# 3_HV_Detection.net
KiCad netlist of a schematic drawn in Altium Designer
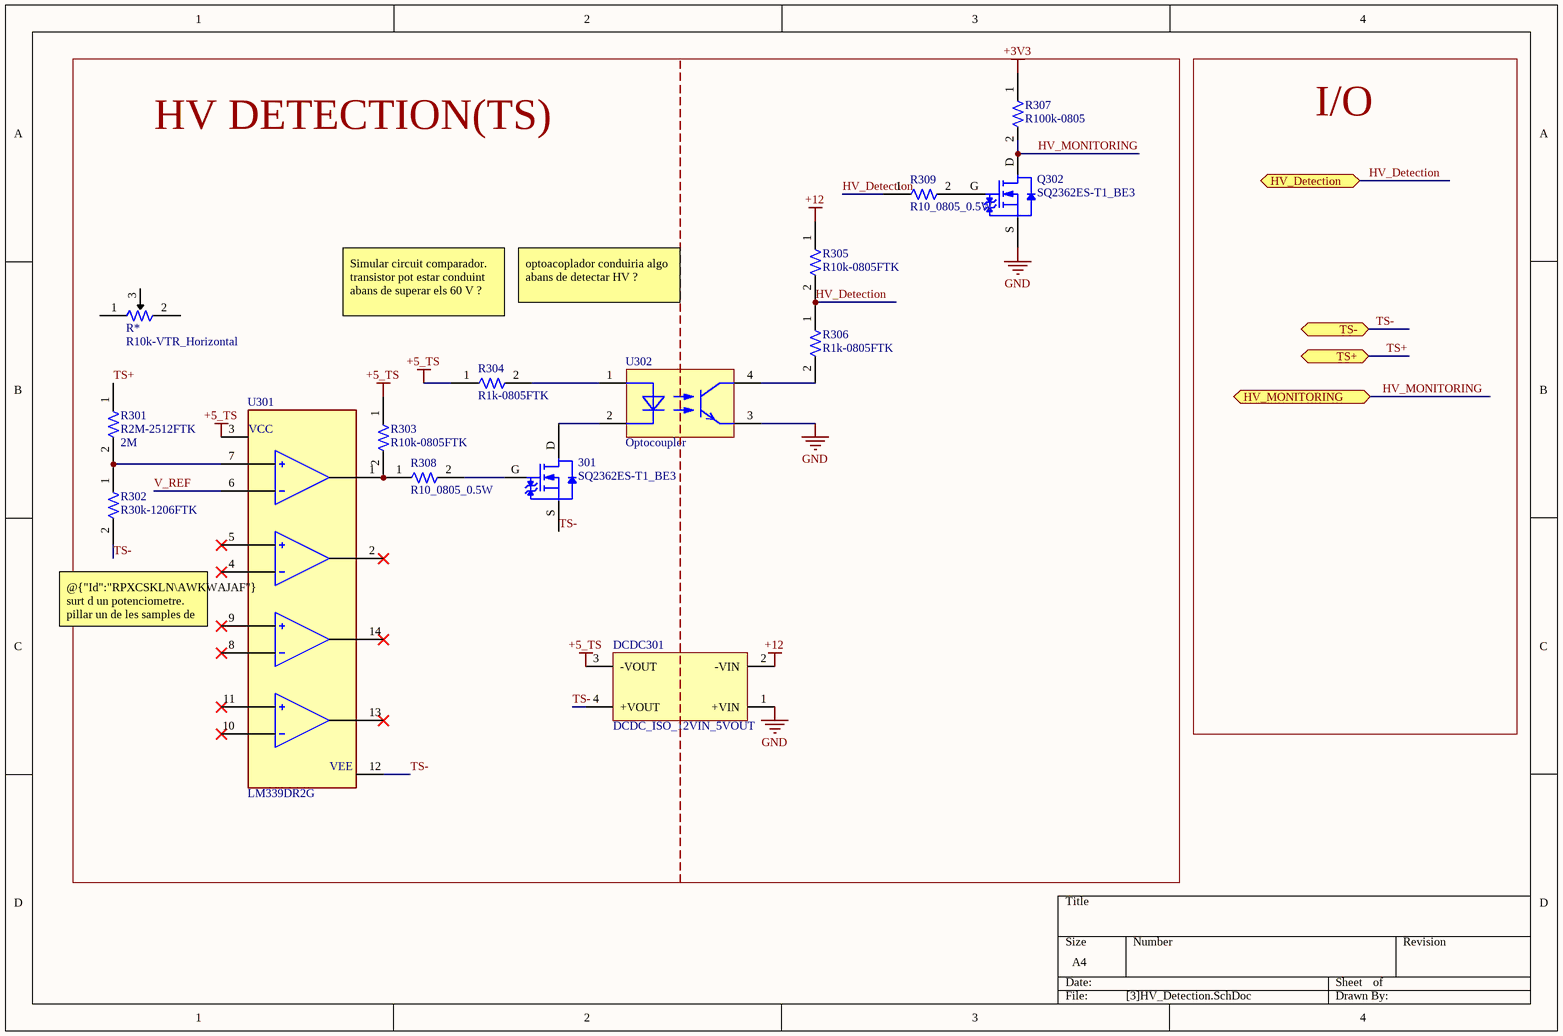
[diagram p0: [3]HV_Detection.SchDoc]

(export (version "E")
  (design (tool "Eeschema 10.0.6"))
  (components
    (comp (ref "301")
      (value "SQ2362ES-T1_BE3")
      (footprint "SOT95P245X110-3N")
      (description "Small Signal Field-Effect Transistor")
      (libsource (lib "EMEA- E-Tech Racing- I'Escola d'Enginyeria de Barcelona Est") (part "TRT-NCH-3/35-CPH"))
    )
    (comp (ref "DCDC301")
      (value "DCDC_ISO_12VIN_5VOUT")
      (footprint "WPME-FISM_SIP-7_L19.65W7.05H10.16")
      (description "WPME-FISM Fixed Isolated SIP/SMT Module")
      (libsource (lib "EMEA- E-Tech Racing- I'Escola d'Enginyeria de Barcelona Est") (part "SIP-7 - WPME-FISM"))
    )
    (comp (ref "Q302")
      (value "SQ2362ES-T1_BE3")
      (footprint "SOT95P245X110-3N")
      (description "Small Signal Field-Effect Transistor")
      (libsource (lib "EMEA- E-Tech Racing- I'Escola d'Enginyeria de Barcelona Est") (part "TRT-NCH-3/35-CPH"))
    )
    (comp (ref "R*")
      (value "R10k-VTR_Horizontal")
      (footprint "T93Z103KT20")
      (description "Trimmer, Cermet, 0.5W, 10000ohm, 10% +/-Tol, 21 Turn(s)")
      (fields (field (name "POWER") "500mW") (field (name "TOLERANCE") "10%"))
      (libsource (lib "EMEA- E-Tech Racing- I'Escola d'Enginyeria de Barcelona Est") (part "R10k-VTR_RM065"))
    )
    (comp (ref "R301")
      (value "R2M-2512FTK")
      (footprint "R2512FTK")
      (description "Current Sense Resistors - SMD 3watts .002ohms 1%")
      (fields
        (field (name "RESISTANCE") "2M")
        (field (name "MANUFACTURER") "Vishay Dale")
        (field (name "TOLERANCE") "1%")
      )
      (libsource (lib "EMEA- E-Tech Racing- I'Escola d'Enginyeria de Barcelona Est") (part "R9.09K-1206FTK"))
    )
    (comp (ref "R302")
      (value "R30k-1206FTK")
      (footprint "R1206FTK-W")
      (description "Res Thick Film 1206 30K Ohm 1% 1/4W ±100ppm/°C Molded SMD SMD Paper T/R")
      (fields
        (field (name "TOLERANCE") "1%")
        (field (name "MANUFACTURER") "Vishay")
        (field (name ".CREATOR") "GP")
      )
      (libsource (lib "EMEA- E-Tech Racing- I'Escola d'Enginyeria de Barcelona Est") (part "R9.09K-1206FTK"))
    )
    (comp (ref "R303")
      (value "R10k-0805FTK")
      (footprint "R0805FTK")
      (fields (field (name "TOLERANCE") "5%") (field (name ".CREATOR") "DR"))
      (libsource (lib "EMEA- E-Tech Racing- I'Escola d'Enginyeria de Barcelona Est") (part "R9.09K-1206FTK"))
    )
    (comp (ref "R304")
      (value "R1k-0805FTK")
      (footprint "R0805FTK")
      (description "Res Thick Film 0805 1K Ohm 5% 1/8W ±200ppm/°C Molded SMD SMD Paper Tape on Plastic Reel")
      (fields (field (name "TOLERANCE") "5%") (field (name ".CREATOR") "GP"))
      (libsource (lib "EMEA- E-Tech Racing- I'Escola d'Enginyeria de Barcelona Est") (part "R9.09K-1206FTK"))
    )
    (comp (ref "R305")
      (value "R10k-0805FTK")
      (footprint "R0805FTK")
      (fields (field (name "TOLERANCE") "5%") (field (name ".CREATOR") "DR"))
      (libsource (lib "EMEA- E-Tech Racing- I'Escola d'Enginyeria de Barcelona Est") (part "R9.09K-1206FTK"))
    )
    (comp (ref "R306")
      (value "R1k-0805FTK")
      (footprint "R0805FTK")
      (description "Res Thick Film 0805 1K Ohm 5% 1/8W ±200ppm/°C Molded SMD SMD Paper Tape on Plastic Reel")
      (fields (field (name "TOLERANCE") "5%") (field (name ".CREATOR") "GP"))
      (libsource (lib "EMEA- E-Tech Racing- I'Escola d'Enginyeria de Barcelona Est") (part "R9.09K-1206FTK"))
    )
    (comp (ref "R307")
      (value "R100k-0805")
      (footprint "RESC2013X70X40NL20T20")
      (fields (field (name "POWER") "125mW") (field (name "TOLERANCE") "5%"))
      (libsource (lib "EMEA- E-Tech Racing- I'Escola d'Enginyeria de Barcelona Est") (part "R9.09K-1206FTK"))
    )
    (comp (ref "R308")
      (value "R10_0805_0.5W")
      (footprint "0805")
      (fields (field (name "TOLERANCE") "1%") (field (name "POWER") "500mW"))
      (libsource (lib "EMEA- E-Tech Racing- I'Escola d'Enginyeria de Barcelona Est") (part "R9.09K-1206FTK"))
    )
    (comp (ref "R309")
      (value "R10_0805_0.5W")
      (footprint "0805")
      (fields (field (name "TOLERANCE") "1%") (field (name "POWER") "500mW"))
      (libsource (lib "EMEA- E-Tech Racing- I'Escola d'Enginyeria de Barcelona Est") (part "R9.09K-1206FTK"))
    )
    (comp (ref "U301")
      (value "LM339DR2G")
      (footprint "ONSC-SOIC-14-751A-03_V")
      (description "Comparator, 4 Func, 9000uV Offset-Max, 1300ns Response Time, BIPolar, PDSO14")
      (libsource (lib "EMEA- E-Tech Racing- I'Escola d'Enginyeria de Barcelona Est") (part "LM339DR2G"))
    )
    (comp (ref "U302")
      (value "Optocoupler")
      (footprint "WL-OCPT_LSOP4")
      (description "Transistor Output Optocoupler. S/N: 140100146000")
      (libsource (lib "EMEA- E-Tech Racing- I'Escola d'Enginyeria de Barcelona Est") (part "Optocoupler Phototransistor_DC_1 Channel"))
    )
  )
  (nets
    (net (code "1") (name "+3V3") (class "Default")
      (node (ref "R307") (pin "1") (pinfunction "1_1") (pintype "passive"))
    )
    (net (code "2") (name "+5_TS") (class "Default")
      (node (ref "DCDC301") (pin "3") (pinfunction "-VOUT_3") (pintype "passive"))
      (node (ref "R303") (pin "1") (pinfunction "1_1") (pintype "passive"))
      (node (ref "R304") (pin "1") (pinfunction "1_1") (pintype "passive"))
      (node (ref "U301") (pin "3") (pinfunction "VCC+_3") (pintype "power_in"))
    )
    (net (code "3") (name "+12") (class "Default")
      (node (ref "DCDC301") (pin "2") (pinfunction "-VIN_2") (pintype "passive"))
      (node (ref "R305") (pin "1") (pinfunction "1_1") (pintype "passive"))
    )
    (net (code "4") (name "/HV_Detection") (class "Default")
      (node (ref "R305") (pin "2") (pinfunction "2_2") (pintype "passive"))
      (node (ref "R306") (pin "1") (pinfunction "1_1") (pintype "passive"))
      (node (ref "R309") (pin "1") (pinfunction "1_1") (pintype "passive"))
    )
    (net (code "5") (name "/HV_MONITORING") (class "Default")
      (node (ref "Q302") (pin "D") (pinfunction "D_D") (pintype "passive"))
      (node (ref "R307") (pin "2") (pinfunction "2_2") (pintype "passive"))
    )
    (net (code "6") (name "/TS+") (class "Default")
      (node (ref "R301") (pin "1") (pinfunction "1_1") (pintype "passive"))
    )
    (net (code "7") (name "/TS-") (class "Default")
      (node (ref "301") (pin "S") (pinfunction "S_S") (pintype "passive"))
      (node (ref "DCDC301") (pin "4") (pinfunction "+VOUT_4") (pintype "passive"))
      (node (ref "R302") (pin "2") (pinfunction "2_2") (pintype "passive"))
      (node (ref "U301") (pin "12") (pinfunction "VEE_12") (pintype "power_in"))
    )
    (net (code "8") (name "/V_REF") (class "Default")
      (node (ref "U301") (pin "6") (pinfunction "1IN-_6") (pintype "tri_state"))
    )
    (net (code "9") (name "GND") (class "Default")
      (node (ref "DCDC301") (pin "1") (pinfunction "+VIN_1") (pintype "passive"))
      (node (ref "Q302") (pin "S") (pinfunction "S_S") (pintype "passive"))
      (node (ref "U302") (pin "3") (pinfunction "Emitter_3") (pintype "passive"))
    )
    (net (code "10") (name "Net-(301-PadG)") (class "Default")
      (node (ref "301") (pin "G") (pinfunction "G_G") (pintype "passive"))
      (node (ref "R308") (pin "2") (pinfunction "2_2") (pintype "passive"))
    )
    (net (code "11") (name "Net-(Q302-PadG)") (class "Default")
      (node (ref "Q302") (pin "G") (pinfunction "G_G") (pintype "passive"))
      (node (ref "R309") (pin "2") (pinfunction "2_2") (pintype "passive"))
    )
    (net (code "12") (name "Net-(U301-1IN+)") (class "Default")
      (node (ref "R301") (pin "2") (pinfunction "2_2") (pintype "passive"))
      (node (ref "R302") (pin "1") (pinfunction "1_1") (pintype "passive"))
      (node (ref "U301") (pin "7") (pinfunction "1IN+_7") (pintype "tri_state"))
    )
    (net (code "13") (name "Net-(U301-1OUT)") (class "Default")
      (node (ref "R303") (pin "2") (pinfunction "2_2") (pintype "passive"))
      (node (ref "R308") (pin "1") (pinfunction "1_1") (pintype "passive"))
      (node (ref "U301") (pin "1") (pinfunction "1OUT_1") (pintype "passive"))
    )
    (net (code "14") (name "Net-(U302-Anode)") (class "Default")
      (node (ref "R304") (pin "2") (pinfunction "2_2") (pintype "passive"))
      (node (ref "U302") (pin "1") (pinfunction "Anode_1") (pintype "passive"))
    )
    (net (code "15") (name "Net-(U302-Cathode)") (class "Default")
      (node (ref "301") (pin "D") (pinfunction "D_D") (pintype "passive"))
      (node (ref "U302") (pin "2") (pinfunction "Cathode_2") (pintype "passive"))
    )
    (net (code "16") (name "Net-(U302-Collector)") (class "Default")
      (node (ref "R306") (pin "2") (pinfunction "2_2") (pintype "passive"))
      (node (ref "U302") (pin "4") (pinfunction "Collector_4") (pintype "passive"))
    )
    (net (code "17") (name "unconnected-(R*-2-Pad1)") (class "Default")
      (node (ref "R*") (pin "1") (pinfunction "2_1") (pintype "passive"))
    )
    (net (code "18") (name "unconnected-(R*-Pad2)") (class "Default")
      (node (ref "R*") (pin "2") (pinfunction "2_2") (pintype "passive"))
    )
    (net (code "19") (name "unconnected-(R*-Pad3)") (class "Default")
      (node (ref "R*") (pin "3") (pinfunction "3_3") (pintype "passive"))
    )
    (net (code "20") (name "unconnected-(U301-2IN+-Pad5)") (class "Default")
      (node (ref "U301") (pin "5") (pinfunction "2IN+_5") (pintype "tri_state+no_connect"))
    )
    (net (code "21") (name "unconnected-(U301-2IN--Pad4)") (class "Default")
      (node (ref "U301") (pin "4") (pinfunction "2IN-_4") (pintype "tri_state+no_connect"))
    )
    (net (code "22") (name "unconnected-(U301-2OUT-Pad2)") (class "Default")
      (node (ref "U301") (pin "2") (pinfunction "2OUT_2") (pintype "passive+no_connect"))
    )
    (net (code "23") (name "unconnected-(U301-3IN+-Pad9)") (class "Default")
      (node (ref "U301") (pin "9") (pinfunction "3IN+_9") (pintype "tri_state+no_connect"))
    )
    (net (code "24") (name "unconnected-(U301-3IN--Pad8)") (class "Default")
      (node (ref "U301") (pin "8") (pinfunction "3IN-_8") (pintype "tri_state+no_connect"))
    )
    (net (code "25") (name "unconnected-(U301-4IN+-Pad11)") (class "Default")
      (node (ref "U301") (pin "11") (pinfunction "4IN+_11") (pintype "tri_state+no_connect"))
    )
    (net (code "26") (name "unconnected-(U301-4IN--Pad10)") (class "Default")
      (node (ref "U301") (pin "10") (pinfunction "4IN-_10") (pintype "tri_state+no_connect"))
    )
    (net (code "27") (name "unconnected-(U301-13OUT-Pad13)") (class "Default")
      (node (ref "U301") (pin "13") (pinfunction "13OUT_13") (pintype "passive+no_connect"))
    )
    (net (code "28") (name "unconnected-(U301-14OUT-Pad14)") (class "Default")
      (node (ref "U301") (pin "14") (pinfunction "14OUT_14") (pintype "passive+no_connect"))
    )
  )
)
